# SelfBalance_V3.net
KiCad netlist of a schematic drawn in EAGLE
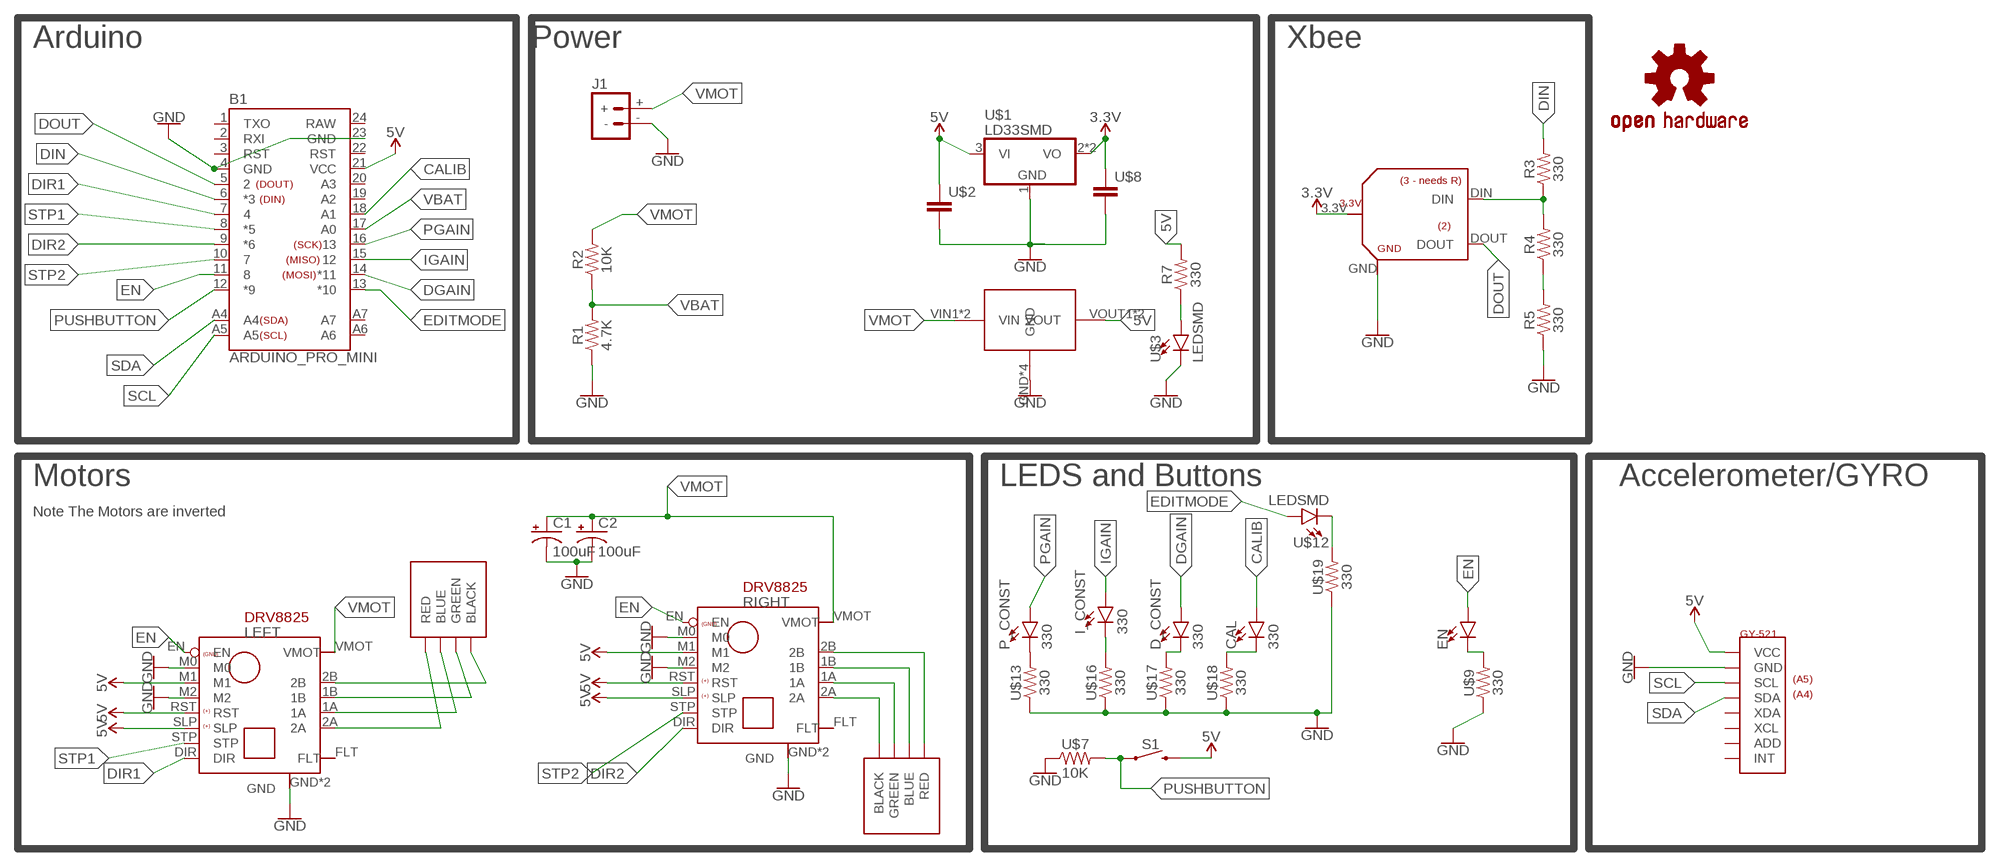
[diagram p0: schematic, sheet 1]

(export (version "E")
  (design (tool "Eeschema 10.0.6"))
  (components
    (comp (ref "B1")
      (value "ARDUINO_PRO_MINI")
      (footprint "eagle-import:ARDUINO_PRO_MINI")
      (libsource (lib "eagle-import") (part "ARDUINO_PRO_MINI"))
    )
    (comp (ref "C1")
      (value "100uF")
      (footprint "eagle-import:CAP_E")
      (libsource (lib "eagle-import") (part "CAP_E"))
    )
    (comp (ref "C2")
      (value "100uF")
      (footprint "eagle-import:CAP_E")
      (libsource (lib "eagle-import") (part "CAP_E"))
    )
    (comp (ref "CAL")
      (value "330")
      (footprint "eagle-import:LED_SMD")
      (libsource (lib "eagle-import") (part "LEDSMD"))
    )
    (comp (ref "D_CONST")
      (value "330")
      (footprint "eagle-import:LED_SMD")
      (libsource (lib "eagle-import") (part "LEDSMD"))
    )
    (comp (ref "EN")
      (value "LEDSMD")
      (footprint "eagle-import:LED_SMD")
      (libsource (lib "eagle-import") (part "LEDSMD"))
    )
    (comp (ref "I_CONST")
      (value "330")
      (footprint "eagle-import:LED_SMD")
      (libsource (lib "eagle-import") (part "LEDSMD"))
    )
    (comp (ref "J1")
      (value "BATTERY_CONNMALE")
      (footprint "eagle-import:DEANS_MALE")
      (libsource (lib "eagle-import") (part "BATTERY_CONNMALE"))
    )
    (comp (ref "LEFT")
      (value "DRV8825")
      (footprint "eagle-import:DRV8825")
      (libsource (lib "eagle-import") (part "DRV8825"))
    )
    (comp (ref "LOGO1")
      (value "OSHW-LOGOL")
      (footprint "eagle-import:OSHW-LOGO-L")
      (libsource (lib "eagle-import") (part "OSHW-LOGOL"))
    )
    (comp (ref "P_CONST")
      (value "330")
      (footprint "eagle-import:LED_SMD")
      (libsource (lib "eagle-import") (part "LEDSMD"))
    )
    (comp (ref "R1")
      (value "4.7K")
      (footprint "eagle-import:R1206")
      (libsource (lib "eagle-import") (part "RESISTORSMD"))
    )
    (comp (ref "R2")
      (value "10K")
      (footprint "eagle-import:R1206")
      (libsource (lib "eagle-import") (part "RESISTORSMD"))
    )
    (comp (ref "R3")
      (value "330")
      (footprint "eagle-import:R1206")
      (libsource (lib "eagle-import") (part "RESISTORSMD"))
    )
    (comp (ref "R4")
      (value "330")
      (footprint "eagle-import:R1206")
      (libsource (lib "eagle-import") (part "RESISTORSMD"))
    )
    (comp (ref "R5")
      (value "330")
      (footprint "eagle-import:R1206")
      (libsource (lib "eagle-import") (part "RESISTORSMD"))
    )
    (comp (ref "R7")
      (value "330")
      (footprint "eagle-import:R1206")
      (libsource (lib "eagle-import") (part "RESISTORSMD"))
    )
    (comp (ref "RIGHT")
      (value "DRV8825")
      (footprint "eagle-import:DRV8825")
      (libsource (lib "eagle-import") (part "DRV8825"))
    )
    (comp (ref "S1")
      (value "PUSH_BUTTON6MM")
      (footprint "eagle-import:BUTTON_6MM")
      (libsource (lib "eagle-import") (part "PUSH_BUTTON6MM"))
    )
    (comp (ref "U$1")
      (value "LD33SMD")
      (footprint "eagle-import:SOT223")
      (libsource (lib "eagle-import") (part "LD33SMD"))
    )
    (comp (ref "U$2")
      (value "CAP_SMCAP")
      (footprint "eagle-import:C1206")
      (libsource (lib "eagle-import") (part "CAP_SMCAP"))
    )
    (comp (ref "U$3")
      (value "LEDSMD")
      (footprint "eagle-import:LED_SMD")
      (libsource (lib "eagle-import") (part "LEDSMD"))
    )
    (comp (ref "U$4")
      (value "STEPDOWNGREEN")
      (footprint "eagle-import:STEPDOWN")
      (libsource (lib "eagle-import") (part "STEPDOWNGREEN"))
    )
    (comp (ref "U$5")
      (value "GY-521")
      (footprint "eagle-import:GY-521")
      (libsource (lib "eagle-import") (part "GY-521"))
    )
    (comp (ref "U$6")
      (value "XBEE_BOUT")
      (footprint "eagle-import:XBEE_BOUT")
      (libsource (lib "eagle-import") (part "XBEE_BOUT"))
    )
    (comp (ref "U$7")
      (value "10K")
      (footprint "eagle-import:R1206")
      (libsource (lib "eagle-import") (part "RESISTORSMD"))
    )
    (comp (ref "U$8")
      (value "CAP_SMCAP")
      (footprint "eagle-import:C1206")
      (libsource (lib "eagle-import") (part "CAP_SMCAP"))
    )
    (comp (ref "U$9")
      (value "330")
      (footprint "eagle-import:R1206")
      (libsource (lib "eagle-import") (part "RESISTORSMD"))
    )
    (comp (ref "U$12")
      (value "LEDSMD")
      (footprint "eagle-import:LED_SMD")
      (libsource (lib "eagle-import") (part "LEDSMD"))
    )
    (comp (ref "U$13")
      (value "330")
      (footprint "eagle-import:R1206")
      (libsource (lib "eagle-import") (part "RESISTORSMD"))
    )
    (comp (ref "U$14")
      (value "STEPPER")
      (footprint "eagle-import:2X4")
      (libsource (lib "eagle-import") (part "STEPPER"))
    )
    (comp (ref "U$15")
      (value "STEPPER")
      (footprint "eagle-import:2X4")
      (libsource (lib "eagle-import") (part "STEPPER"))
    )
    (comp (ref "U$16")
      (value "330")
      (footprint "eagle-import:R1206")
      (libsource (lib "eagle-import") (part "RESISTORSMD"))
    )
    (comp (ref "U$17")
      (value "330")
      (footprint "eagle-import:R1206")
      (libsource (lib "eagle-import") (part "RESISTORSMD"))
    )
    (comp (ref "U$18")
      (value "330")
      (footprint "eagle-import:R1206")
      (libsource (lib "eagle-import") (part "RESISTORSMD"))
    )
    (comp (ref "U$19")
      (value "330")
      (footprint "eagle-import:R1206")
      (libsource (lib "eagle-import") (part "RESISTORSMD"))
    )
  )
  (nets
    (net (code "1") (name "/RAW") (class "Default")
      (node (ref "B1") (pin "24") (pinfunction "RAW_24") (pintype "power_in"))
    )
    (net (code "2") (name "3.3V") (class "Default")
      (node (ref "U$1") (pin "2") (pinfunction "VO_2") (pintype "passive"))
      (node (ref "U$1") (pin "4") (pinfunction "VO_4") (pintype "passive"))
      (node (ref "U$6") (pin "3.3V") (pinfunction "3.3V_3.3V") (pintype "bidirectional"))
      (node (ref "U$8") (pin "1") (pinfunction "1_1") (pintype "passive"))
    )
    (net (code "3") (name "5V") (class "Default")
      (node (ref "B1") (pin "21") (pinfunction "VCC_21") (pintype "power_in"))
      (node (ref "LEFT") (pin "M1") (pinfunction "M1_M1") (pintype "passive"))
      (node (ref "LEFT") (pin "RST") (pinfunction "RST_RST") (pintype "passive"))
      (node (ref "LEFT") (pin "SLP") (pinfunction "SLP_SLP") (pintype "passive"))
      (node (ref "R7") (pin "2") (pinfunction "2_2") (pintype "passive"))
      (node (ref "RIGHT") (pin "M1") (pinfunction "M1_M1") (pintype "passive"))
      (node (ref "RIGHT") (pin "RST") (pinfunction "RST_RST") (pintype "passive"))
      (node (ref "RIGHT") (pin "SLP") (pinfunction "SLP_SLP") (pintype "passive"))
      (node (ref "S1") (pin "3") (pinfunction "2_3") (pintype "passive"))
      (node (ref "U$1") (pin "3") (pinfunction "VI_3") (pintype "input"))
      (node (ref "U$2") (pin "1") (pinfunction "1_1") (pintype "passive"))
      (node (ref "U$4") (pin "VOUT1") (pinfunction "VOUT_VOUT1") (pintype "passive"))
      (node (ref "U$4") (pin "VOUT2") (pinfunction "VOUT_VOUT2") (pintype "passive"))
      (node (ref "U$5") (pin "VCC") (pinfunction "VCC_VCC") (pintype "passive"))
    )
    (net (code "4") (name "CALIB") (class "Default")
      (node (ref "B1") (pin "18") (pinfunction "A1_18") (pintype "bidirectional"))
      (node (ref "CAL") (pin "A") (pinfunction "A_A") (pintype "passive"))
    )
    (net (code "5") (name "DGAIN") (class "Default")
      (node (ref "B1") (pin "14") (pinfunction "*11_14") (pintype "bidirectional"))
      (node (ref "D_CONST") (pin "A") (pinfunction "A_A") (pintype "passive"))
    )
    (net (code "6") (name "DIN") (class "Default")
      (node (ref "B1") (pin "6") (pinfunction "*3_6") (pintype "bidirectional"))
      (node (ref "R3") (pin "2") (pinfunction "2_2") (pintype "passive"))
    )
    (net (code "7") (name "DIR1") (class "Default")
      (node (ref "B1") (pin "7") (pinfunction "4_7") (pintype "bidirectional"))
      (node (ref "LEFT") (pin "DIR") (pinfunction "DIR_DIR") (pintype "passive"))
    )
    (net (code "8") (name "DIR2") (class "Default")
      (node (ref "B1") (pin "9") (pinfunction "*6_9") (pintype "bidirectional"))
      (node (ref "RIGHT") (pin "DIR") (pinfunction "DIR_DIR") (pintype "passive"))
    )
    (net (code "9") (name "DOUT") (class "Default")
      (node (ref "B1") (pin "5") (pinfunction "2_5") (pintype "bidirectional"))
      (node (ref "U$6") (pin "DOUT") (pinfunction "DOUT_DOUT") (pintype "bidirectional"))
    )
    (net (code "10") (name "EDITMODE") (class "Default")
      (node (ref "B1") (pin "13") (pinfunction "*10_13") (pintype "bidirectional"))
      (node (ref "U$12") (pin "A") (pinfunction "A_A") (pintype "passive"))
    )
    (net (code "11") (name "EN") (class "Default")
      (node (ref "B1") (pin "11") (pinfunction "8_11") (pintype "bidirectional"))
      (node (ref "EN") (pin "A") (pinfunction "A_A") (pintype "passive"))
      (node (ref "LEFT") (pin "EN") (pinfunction "EN_EN") (pintype "passive"))
      (node (ref "RIGHT") (pin "EN") (pinfunction "EN_EN") (pintype "passive"))
    )
    (net (code "12") (name "GND") (class "Default")
      (node (ref "B1") (pin "23") (pinfunction "GND_23") (pintype "power_in"))
      (node (ref "B1") (pin "4") (pinfunction "GND_4") (pintype "power_in"))
      (node (ref "C1") (pin "-") (pinfunction "-_-") (pintype "passive"))
      (node (ref "C2") (pin "-") (pinfunction "-_-") (pintype "passive"))
      (node (ref "J1") (pin "-") (pinfunction "-_-") (pintype "passive"))
      (node (ref "LEFT") (pin "GND") (pinfunction "GND_GND") (pintype "passive"))
      (node (ref "LEFT") (pin "GND2") (pinfunction "GND_GND2") (pintype "passive"))
      (node (ref "LEFT") (pin "M0") (pinfunction "M0_M0") (pintype "passive"))
      (node (ref "LEFT") (pin "M2") (pinfunction "M2_M2") (pintype "passive"))
      (node (ref "R1") (pin "1") (pinfunction "1_1") (pintype "passive"))
      (node (ref "R5") (pin "1") (pinfunction "1_1") (pintype "passive"))
      (node (ref "RIGHT") (pin "GND") (pinfunction "GND_GND") (pintype "passive"))
      (node (ref "RIGHT") (pin "GND2") (pinfunction "GND_GND2") (pintype "passive"))
      (node (ref "RIGHT") (pin "M0") (pinfunction "M0_M0") (pintype "passive"))
      (node (ref "RIGHT") (pin "M2") (pinfunction "M2_M2") (pintype "passive"))
      (node (ref "U$1") (pin "1") (pinfunction "GND_1") (pintype "passive"))
      (node (ref "U$13") (pin "1") (pinfunction "1_1") (pintype "passive"))
      (node (ref "U$16") (pin "1") (pinfunction "1_1") (pintype "passive"))
      (node (ref "U$17") (pin "1") (pinfunction "1_1") (pintype "passive"))
      (node (ref "U$18") (pin "1") (pinfunction "1_1") (pintype "passive"))
      (node (ref "U$19") (pin "1") (pinfunction "1_1") (pintype "passive"))
      (node (ref "U$2") (pin "2") (pinfunction "2_2") (pintype "passive"))
      (node (ref "U$3") (pin "C") (pinfunction "C_C") (pintype "passive"))
      (node (ref "U$4") (pin "GND") (pinfunction "GND_GND") (pintype "passive"))
      (node (ref "U$4") (pin "GND2") (pinfunction "GND_GND2") (pintype "passive"))
      (node (ref "U$4") (pin "GND3") (pinfunction "GND_GND3") (pintype "passive"))
      (node (ref "U$4") (pin "GND4") (pinfunction "GND_GND4") (pintype "passive"))
      (node (ref "U$5") (pin "GND") (pinfunction "GND_GND") (pintype "passive"))
      (node (ref "U$6") (pin "GND") (pinfunction "GND_GND") (pintype "bidirectional"))
      (node (ref "U$7") (pin "1") (pinfunction "1_1") (pintype "passive"))
      (node (ref "U$8") (pin "2") (pinfunction "2_2") (pintype "passive"))
      (node (ref "U$9") (pin "1") (pinfunction "1_1") (pintype "passive"))
    )
    (net (code "13") (name "IGAIN") (class "Default")
      (node (ref "B1") (pin "15") (pinfunction "12_15") (pintype "bidirectional"))
      (node (ref "I_CONST") (pin "A") (pinfunction "A_A") (pintype "passive"))
    )
    (net (code "14") (name "Net-(CAL-PadC)") (class "Default")
      (node (ref "CAL") (pin "C") (pinfunction "C_C") (pintype "passive"))
      (node (ref "U$18") (pin "2") (pinfunction "2_2") (pintype "passive"))
    )
    (net (code "15") (name "Net-(D_CONST-PadC)") (class "Default")
      (node (ref "D_CONST") (pin "C") (pinfunction "C_C") (pintype "passive"))
      (node (ref "U$17") (pin "2") (pinfunction "2_2") (pintype "passive"))
    )
    (net (code "16") (name "Net-(EN-PadC)") (class "Default")
      (node (ref "EN") (pin "C") (pinfunction "C_C") (pintype "passive"))
      (node (ref "U$9") (pin "2") (pinfunction "2_2") (pintype "passive"))
    )
    (net (code "17") (name "Net-(I_CONST-PadC)") (class "Default")
      (node (ref "I_CONST") (pin "C") (pinfunction "C_C") (pintype "passive"))
      (node (ref "U$16") (pin "2") (pinfunction "2_2") (pintype "passive"))
    )
    (net (code "18") (name "Net-(LEFT-Pad1A)") (class "Default")
      (node (ref "LEFT") (pin "1A") (pinfunction "1A_1A") (pintype "passive"))
      (node (ref "U$14") (pin "U1") (pinfunction "BLUE_U1") (pintype "passive"))
      (node (ref "U$14") (pin "U2") (pinfunction "BLUE_U2") (pintype "passive"))
    )
    (net (code "19") (name "Net-(LEFT-Pad1B)") (class "Default")
      (node (ref "LEFT") (pin "1B") (pinfunction "1B_1B") (pintype "passive"))
      (node (ref "U$14") (pin "G1") (pinfunction "GREEN_G1") (pintype "passive"))
      (node (ref "U$14") (pin "G2") (pinfunction "GREEN_G2") (pintype "passive"))
    )
    (net (code "20") (name "Net-(LEFT-Pad2A)") (class "Default")
      (node (ref "LEFT") (pin "2A") (pinfunction "2A_2A") (pintype "passive"))
      (node (ref "U$14") (pin "R1") (pinfunction "RED_R1") (pintype "passive"))
      (node (ref "U$14") (pin "R2") (pinfunction "RED_R2") (pintype "passive"))
    )
    (net (code "21") (name "Net-(LEFT-Pad2B)") (class "Default")
      (node (ref "LEFT") (pin "2B") (pinfunction "2B_2B") (pintype "passive"))
      (node (ref "U$14") (pin "B1") (pinfunction "BLACK_B1") (pintype "passive"))
      (node (ref "U$14") (pin "B2") (pinfunction "BLACK_B2") (pintype "passive"))
    )
    (net (code "22") (name "Net-(P_CONST-PadC)") (class "Default")
      (node (ref "P_CONST") (pin "C") (pinfunction "C_C") (pintype "passive"))
      (node (ref "U$13") (pin "2") (pinfunction "2_2") (pintype "passive"))
    )
    (net (code "23") (name "Net-(R3-Pad1)") (class "Default")
      (node (ref "R3") (pin "1") (pinfunction "1_1") (pintype "passive"))
      (node (ref "R4") (pin "2") (pinfunction "2_2") (pintype "passive"))
      (node (ref "U$6") (pin "DIN") (pinfunction "DIN_DIN") (pintype "bidirectional"))
    )
    (net (code "24") (name "Net-(R4-Pad1)") (class "Default")
      (node (ref "R4") (pin "1") (pinfunction "1_1") (pintype "passive"))
      (node (ref "R5") (pin "2") (pinfunction "2_2") (pintype "passive"))
    )
    (net (code "25") (name "Net-(R7-Pad1)") (class "Default")
      (node (ref "R7") (pin "1") (pinfunction "1_1") (pintype "passive"))
      (node (ref "U$3") (pin "A") (pinfunction "A_A") (pintype "passive"))
    )
    (net (code "26") (name "Net-(RIGHT-Pad1A)") (class "Default")
      (node (ref "RIGHT") (pin "1A") (pinfunction "1A_1A") (pintype "passive"))
      (node (ref "U$15") (pin "G1") (pinfunction "GREEN_G1") (pintype "passive"))
      (node (ref "U$15") (pin "G2") (pinfunction "GREEN_G2") (pintype "passive"))
    )
    (net (code "27") (name "Net-(RIGHT-Pad1B)") (class "Default")
      (node (ref "RIGHT") (pin "1B") (pinfunction "1B_1B") (pintype "passive"))
      (node (ref "U$15") (pin "U1") (pinfunction "BLUE_U1") (pintype "passive"))
      (node (ref "U$15") (pin "U2") (pinfunction "BLUE_U2") (pintype "passive"))
    )
    (net (code "28") (name "Net-(RIGHT-Pad2A)") (class "Default")
      (node (ref "RIGHT") (pin "2A") (pinfunction "2A_2A") (pintype "passive"))
      (node (ref "U$15") (pin "B1") (pinfunction "BLACK_B1") (pintype "passive"))
      (node (ref "U$15") (pin "B2") (pinfunction "BLACK_B2") (pintype "passive"))
    )
    (net (code "29") (name "Net-(RIGHT-Pad2B)") (class "Default")
      (node (ref "RIGHT") (pin "2B") (pinfunction "2B_2B") (pintype "passive"))
      (node (ref "U$15") (pin "R1") (pinfunction "RED_R1") (pintype "passive"))
      (node (ref "U$15") (pin "R2") (pinfunction "RED_R2") (pintype "passive"))
    )
    (net (code "30") (name "Net-(U$12-PadC)") (class "Default")
      (node (ref "U$12") (pin "C") (pinfunction "C_C") (pintype "passive"))
      (node (ref "U$19") (pin "2") (pinfunction "2_2") (pintype "passive"))
    )
    (net (code "31") (name "PGAIN") (class "Default")
      (node (ref "B1") (pin "16") (pinfunction "13_16") (pintype "bidirectional"))
      (node (ref "P_CONST") (pin "A") (pinfunction "A_A") (pintype "passive"))
    )
    (net (code "32") (name "PUSHBUTTON") (class "Default")
      (node (ref "B1") (pin "12") (pinfunction "*9_12") (pintype "bidirectional"))
      (node (ref "S1") (pin "1") (pinfunction "1_1") (pintype "passive"))
      (node (ref "U$7") (pin "2") (pinfunction "2_2") (pintype "passive"))
    )
    (net (code "33") (name "SCL") (class "Default")
      (node (ref "B1") (pin "A5") (pinfunction "A5_A5") (pintype "bidirectional"))
      (node (ref "U$5") (pin "SCL") (pinfunction "SCL_SCL") (pintype "passive"))
    )
    (net (code "34") (name "SDA") (class "Default")
      (node (ref "B1") (pin "A4") (pinfunction "A4_A4") (pintype "bidirectional"))
      (node (ref "U$5") (pin "SDA") (pinfunction "SDA_SDA") (pintype "passive"))
    )
    (net (code "35") (name "STP1") (class "Default")
      (node (ref "B1") (pin "8") (pinfunction "*5_8") (pintype "bidirectional"))
      (node (ref "LEFT") (pin "STP") (pinfunction "STP_STP") (pintype "passive"))
    )
    (net (code "36") (name "STP2") (class "Default")
      (node (ref "B1") (pin "10") (pinfunction "7_10") (pintype "bidirectional"))
      (node (ref "RIGHT") (pin "STP") (pinfunction "STP_STP") (pintype "passive"))
    )
    (net (code "37") (name "VBAT") (class "Default")
      (node (ref "B1") (pin "17") (pinfunction "A0_17") (pintype "bidirectional"))
      (node (ref "R1") (pin "2") (pinfunction "2_2") (pintype "passive"))
      (node (ref "R2") (pin "1") (pinfunction "1_1") (pintype "passive"))
    )
    (net (code "38") (name "VMOT") (class "Default")
      (node (ref "C1") (pin "+") (pinfunction "+_+") (pintype "passive"))
      (node (ref "C2") (pin "+") (pinfunction "+_+") (pintype "passive"))
      (node (ref "J1") (pin "+") (pinfunction "+_+") (pintype "passive"))
      (node (ref "LEFT") (pin "VMOT") (pinfunction "VMOT_VMOT") (pintype "passive"))
      (node (ref "R2") (pin "2") (pinfunction "2_2") (pintype "passive"))
      (node (ref "RIGHT") (pin "VMOT") (pinfunction "VMOT_VMOT") (pintype "passive"))
      (node (ref "U$4") (pin "VIN1") (pinfunction "VIN_VIN1") (pintype "passive"))
      (node (ref "U$4") (pin "VIN2") (pinfunction "VIN_VIN2") (pintype "passive"))
    )
    (net (code "39") (name "unconnected-(B1-A2-Pad19)") (class "Default")
      (node (ref "B1") (pin "19") (pinfunction "A2_19") (pintype "bidirectional"))
    )
    (net (code "40") (name "unconnected-(B1-A3-Pad20)") (class "Default")
      (node (ref "B1") (pin "20") (pinfunction "A3_20") (pintype "bidirectional"))
    )
    (net (code "41") (name "unconnected-(B1-PadA6)") (class "Default")
      (node (ref "B1") (pin "A6") (pinfunction "A6_A6") (pintype "bidirectional"))
    )
    (net (code "42") (name "unconnected-(B1-PadA7)") (class "Default")
      (node (ref "B1") (pin "A7") (pinfunction "A7_A7") (pintype "bidirectional"))
    )
    (net (code "43") (name "unconnected-(B1-RST-Pad3)") (class "Default")
      (node (ref "B1") (pin "3") (pinfunction "RST_3") (pintype "bidirectional"))
    )
    (net (code "44") (name "unconnected-(B1-RST-Pad22)") (class "Default")
      (node (ref "B1") (pin "22") (pinfunction "RST_22") (pintype "bidirectional"))
    )
    (net (code "45") (name "unconnected-(B1-RXI-Pad2)") (class "Default")
      (node (ref "B1") (pin "2") (pinfunction "RXI_2") (pintype "bidirectional"))
    )
    (net (code "46") (name "unconnected-(B1-TXO-Pad1)") (class "Default")
      (node (ref "B1") (pin "1") (pinfunction "TXO_1") (pintype "bidirectional"))
    )
    (net (code "47") (name "unconnected-(LEFT-PadFLT)") (class "Default")
      (node (ref "LEFT") (pin "FLT") (pinfunction "FLT_FLT") (pintype "passive"))
    )
    (net (code "48") (name "unconnected-(RIGHT-PadFLT)") (class "Default")
      (node (ref "RIGHT") (pin "FLT") (pinfunction "FLT_FLT") (pintype "passive"))
    )
    (net (code "49") (name "unconnected-(U$5-PadADD)") (class "Default")
      (node (ref "U$5") (pin "ADD") (pinfunction "ADD_ADD") (pintype "passive"))
    )
    (net (code "50") (name "unconnected-(U$5-PadINT)") (class "Default")
      (node (ref "U$5") (pin "INT") (pinfunction "INT_INT") (pintype "passive"))
    )
    (net (code "51") (name "unconnected-(U$5-PadXCL)") (class "Default")
      (node (ref "U$5") (pin "XCL") (pinfunction "XCL_XCL") (pintype "passive"))
    )
    (net (code "52") (name "unconnected-(U$5-PadXDA)") (class "Default")
      (node (ref "U$5") (pin "XDA") (pinfunction "XDA_XDA") (pintype "passive"))
    )
  )
)
